# breakout.net
KiCad netlist of a schematic drawn in EAGLE
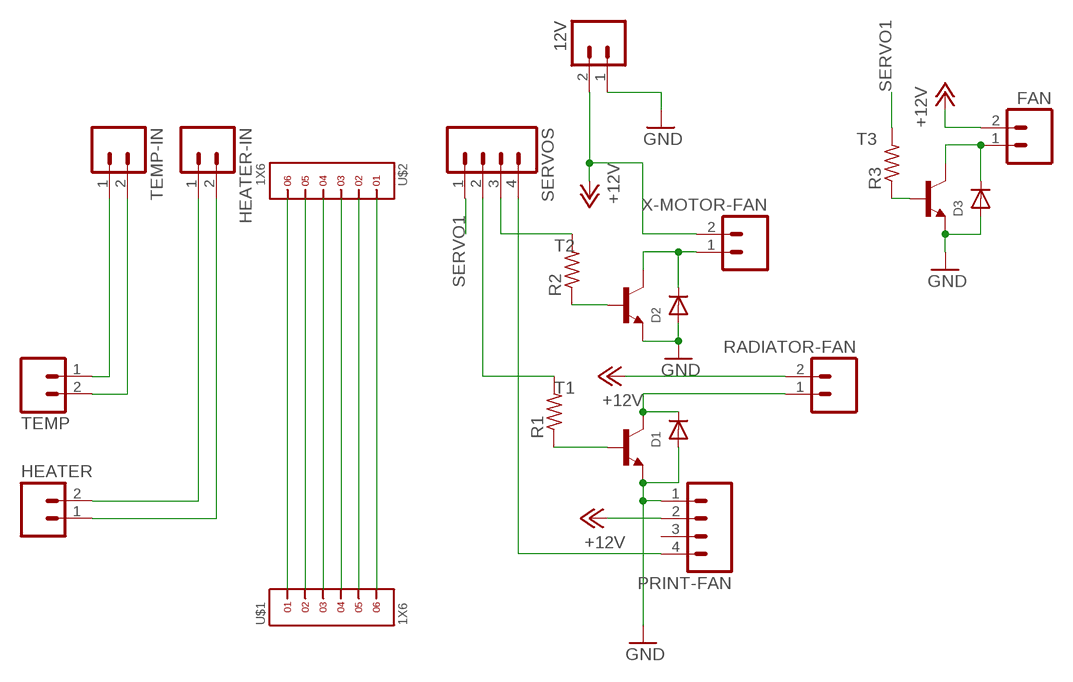
[diagram p0: schematic, sheet 1]

(export (version "E")
  (design (tool "Eeschema 10.0.6"))
  (components
    (comp (ref "12V")
      (value "M02")
      (footprint "eagle-import:02P")
      (libsource (lib "eagle-import") (part "M02"))
    )
    (comp (ref "D1")
      (value "DIODESMA")
      (footprint "eagle-import:SMADIODE")
      (libsource (lib "eagle-import") (part "DIODESMA"))
    )
    (comp (ref "D2")
      (value "DIODESMA")
      (footprint "eagle-import:SMADIODE")
      (libsource (lib "eagle-import") (part "DIODESMA"))
    )
    (comp (ref "D3")
      (value "DIODESMA")
      (footprint "eagle-import:SMADIODE")
      (libsource (lib "eagle-import") (part "DIODESMA"))
    )
    (comp (ref "FAN")
      (value "M02")
      (footprint "eagle-import:02P")
      (libsource (lib "eagle-import") (part "M02"))
    )
    (comp (ref "HEATER")
      (value "M02")
      (footprint "eagle-import:02P")
      (libsource (lib "eagle-import") (part "M02"))
    )
    (comp (ref "HEATER-IN")
      (value "M02")
      (footprint "eagle-import:02P")
      (libsource (lib "eagle-import") (part "M02"))
    )
    (comp (ref "PRINT-FAN")
      (value "M04")
      (footprint "eagle-import:04P")
      (libsource (lib "eagle-import") (part "M04"))
    )
    (comp (ref "R1")
      (value "R-US_R0603")
      (footprint "eagle-import:R0603")
      (libsource (lib "eagle-import") (part "R-US_R0603"))
    )
    (comp (ref "R2")
      (value "R-US_R0603")
      (footprint "eagle-import:R0603")
      (libsource (lib "eagle-import") (part "R-US_R0603"))
    )
    (comp (ref "R3")
      (value "R-US_R0603")
      (footprint "eagle-import:R0603")
      (libsource (lib "eagle-import") (part "R-US_R0603"))
    )
    (comp (ref "RADIATOR-FAN")
      (value "M02")
      (footprint "eagle-import:02P")
      (libsource (lib "eagle-import") (part "M02"))
    )
    (comp (ref "SERVOS")
      (value "M04")
      (footprint "eagle-import:04P")
      (libsource (lib "eagle-import") (part "M04"))
    )
    (comp (ref "T1")
      (value "BC808-NPN-SOT23-BEC")
      (footprint "eagle-import:SOT23-BEC")
      (libsource (lib "eagle-import") (part "-NPN-SOT23-BECBC808"))
    )
    (comp (ref "T2")
      (value "BC808-NPN-SOT23-BEC")
      (footprint "eagle-import:SOT23-BEC")
      (libsource (lib "eagle-import") (part "-NPN-SOT23-BECBC808"))
    )
    (comp (ref "T3")
      (value "BC808-NPN-SOT23-BEC")
      (footprint "eagle-import:SOT23-BEC")
      (libsource (lib "eagle-import") (part "-NPN-SOT23-BECBC808"))
    )
    (comp (ref "TEMP")
      (value "M02")
      (footprint "eagle-import:02P")
      (libsource (lib "eagle-import") (part "M02"))
    )
    (comp (ref "TEMP-IN")
      (value "M02")
      (footprint "eagle-import:02P")
      (libsource (lib "eagle-import") (part "M02"))
    )
    (comp (ref "U$1")
      (value "1X6")
      (footprint "eagle-import:1X6")
      (libsource (lib "eagle-import") (part "1X6"))
    )
    (comp (ref "U$2")
      (value "1X6")
      (footprint "eagle-import:1X6")
      (libsource (lib "eagle-import") (part "1X6"))
    )
    (comp (ref "X-MOTOR-FAN")
      (value "M02")
      (footprint "eagle-import:02P")
      (libsource (lib "eagle-import") (part "M02"))
    )
  )
  (nets
    (net (code "1") (name "+12V") (class "Default")
      (node (ref "12V") (pin "2") (pinfunction "2_2") (pintype "passive"))
      (node (ref "FAN") (pin "2") (pinfunction "2_2") (pintype "passive"))
      (node (ref "PRINT-FAN") (pin "2") (pinfunction "2_2") (pintype "passive"))
      (node (ref "RADIATOR-FAN") (pin "2") (pinfunction "2_2") (pintype "passive"))
      (node (ref "X-MOTOR-FAN") (pin "2") (pinfunction "2_2") (pintype "passive"))
    )
    (net (code "2") (name "/SERVO1") (class "Default")
      (node (ref "R3") (pin "2") (pinfunction "2_2") (pintype "passive"))
      (node (ref "SERVOS") (pin "1") (pinfunction "1_1") (pintype "passive"))
    )
    (net (code "3") (name "GND") (class "Default")
      (node (ref "12V") (pin "1") (pinfunction "1_1") (pintype "passive"))
      (node (ref "D1") (pin "A") (pinfunction "A_A") (pintype "passive"))
      (node (ref "D2") (pin "A") (pinfunction "A_A") (pintype "passive"))
      (node (ref "D3") (pin "A") (pinfunction "A_A") (pintype "passive"))
      (node (ref "PRINT-FAN") (pin "1") (pinfunction "1_1") (pintype "passive"))
      (node (ref "T1") (pin "E") (pinfunction "E_E") (pintype "passive"))
      (node (ref "T2") (pin "E") (pinfunction "E_E") (pintype "passive"))
      (node (ref "T3") (pin "E") (pinfunction "E_E") (pintype "passive"))
    )
    (net (code "4") (name "Net-(D1-PadC)") (class "Default")
      (node (ref "D1") (pin "C") (pinfunction "C_C") (pintype "passive"))
      (node (ref "RADIATOR-FAN") (pin "1") (pinfunction "1_1") (pintype "passive"))
      (node (ref "T1") (pin "C") (pinfunction "C_C") (pintype "passive"))
    )
    (net (code "5") (name "Net-(D2-PadC)") (class "Default")
      (node (ref "D2") (pin "C") (pinfunction "C_C") (pintype "passive"))
      (node (ref "T2") (pin "C") (pinfunction "C_C") (pintype "passive"))
      (node (ref "X-MOTOR-FAN") (pin "1") (pinfunction "1_1") (pintype "passive"))
    )
    (net (code "6") (name "Net-(D3-PadC)") (class "Default")
      (node (ref "D3") (pin "C") (pinfunction "C_C") (pintype "passive"))
      (node (ref "FAN") (pin "1") (pinfunction "1_1") (pintype "passive"))
      (node (ref "T3") (pin "C") (pinfunction "C_C") (pintype "passive"))
    )
    (net (code "7") (name "Net-(HEATER-IN-Pad1)") (class "Default")
      (node (ref "HEATER") (pin "2") (pinfunction "2_2") (pintype "passive"))
      (node (ref "HEATER-IN") (pin "1") (pinfunction "1_1") (pintype "passive"))
    )
    (net (code "8") (name "Net-(HEATER-IN-Pad2)") (class "Default")
      (node (ref "HEATER") (pin "1") (pinfunction "1_1") (pintype "passive"))
      (node (ref "HEATER-IN") (pin "2") (pinfunction "2_2") (pintype "passive"))
    )
    (net (code "9") (name "Net-(PRINT-FAN-Pad4)") (class "Default")
      (node (ref "PRINT-FAN") (pin "4") (pinfunction "4_4") (pintype "passive"))
      (node (ref "SERVOS") (pin "4") (pinfunction "4_4") (pintype "passive"))
    )
    (net (code "10") (name "Net-(R1-Pad1)") (class "Default")
      (node (ref "R1") (pin "1") (pinfunction "1_1") (pintype "passive"))
      (node (ref "T1") (pin "B") (pinfunction "B_B") (pintype "passive"))
    )
    (net (code "11") (name "Net-(R1-Pad2)") (class "Default")
      (node (ref "R1") (pin "2") (pinfunction "2_2") (pintype "passive"))
      (node (ref "SERVOS") (pin "2") (pinfunction "2_2") (pintype "passive"))
    )
    (net (code "12") (name "Net-(R2-Pad1)") (class "Default")
      (node (ref "R2") (pin "1") (pinfunction "1_1") (pintype "passive"))
      (node (ref "T2") (pin "B") (pinfunction "B_B") (pintype "passive"))
    )
    (net (code "13") (name "Net-(R2-Pad2)") (class "Default")
      (node (ref "R2") (pin "2") (pinfunction "2_2") (pintype "passive"))
      (node (ref "SERVOS") (pin "3") (pinfunction "3_3") (pintype "passive"))
    )
    (net (code "14") (name "Net-(R3-Pad1)") (class "Default")
      (node (ref "R3") (pin "1") (pinfunction "1_1") (pintype "passive"))
      (node (ref "T3") (pin "B") (pinfunction "B_B") (pintype "passive"))
    )
    (net (code "15") (name "Net-(TEMP-IN-Pad1)") (class "Default")
      (node (ref "TEMP") (pin "1") (pinfunction "1_1") (pintype "passive"))
      (node (ref "TEMP-IN") (pin "1") (pinfunction "1_1") (pintype "passive"))
    )
    (net (code "16") (name "Net-(TEMP-IN-Pad2)") (class "Default")
      (node (ref "TEMP") (pin "2") (pinfunction "2_2") (pintype "passive"))
      (node (ref "TEMP-IN") (pin "2") (pinfunction "2_2") (pintype "passive"))
    )
    (net (code "17") (name "Net-(U$1-Pad1)") (class "Default")
      (node (ref "U$1") (pin "1") (pinfunction "1_1") (pintype "bidirectional"))
      (node (ref "U$2") (pin "6") (pinfunction "6_6") (pintype "bidirectional"))
    )
    (net (code "18") (name "Net-(U$1-Pad2)") (class "Default")
      (node (ref "U$1") (pin "2") (pinfunction "2_2") (pintype "bidirectional"))
      (node (ref "U$2") (pin "5") (pinfunction "5_5") (pintype "bidirectional"))
    )
    (net (code "19") (name "Net-(U$1-Pad3)") (class "Default")
      (node (ref "U$1") (pin "3") (pinfunction "3_3") (pintype "bidirectional"))
      (node (ref "U$2") (pin "4") (pinfunction "4_4") (pintype "bidirectional"))
    )
    (net (code "20") (name "Net-(U$1-Pad4)") (class "Default")
      (node (ref "U$1") (pin "4") (pinfunction "4_4") (pintype "bidirectional"))
      (node (ref "U$2") (pin "3") (pinfunction "3_3") (pintype "bidirectional"))
    )
    (net (code "21") (name "Net-(U$1-Pad5)") (class "Default")
      (node (ref "U$1") (pin "5") (pinfunction "5_5") (pintype "bidirectional"))
      (node (ref "U$2") (pin "2") (pinfunction "2_2") (pintype "bidirectional"))
    )
    (net (code "22") (name "Net-(U$1-Pad6)") (class "Default")
      (node (ref "U$1") (pin "6") (pinfunction "6_6") (pintype "bidirectional"))
      (node (ref "U$2") (pin "1") (pinfunction "1_1") (pintype "bidirectional"))
    )
    (net (code "23") (name "unconnected-(PRINT-FAN-Pad3)") (class "Default")
      (node (ref "PRINT-FAN") (pin "3") (pinfunction "3_3") (pintype "passive"))
    )
  )
)
